# zigduino-v6c-test.net
KiCad netlist of a schematic drawn in EAGLE
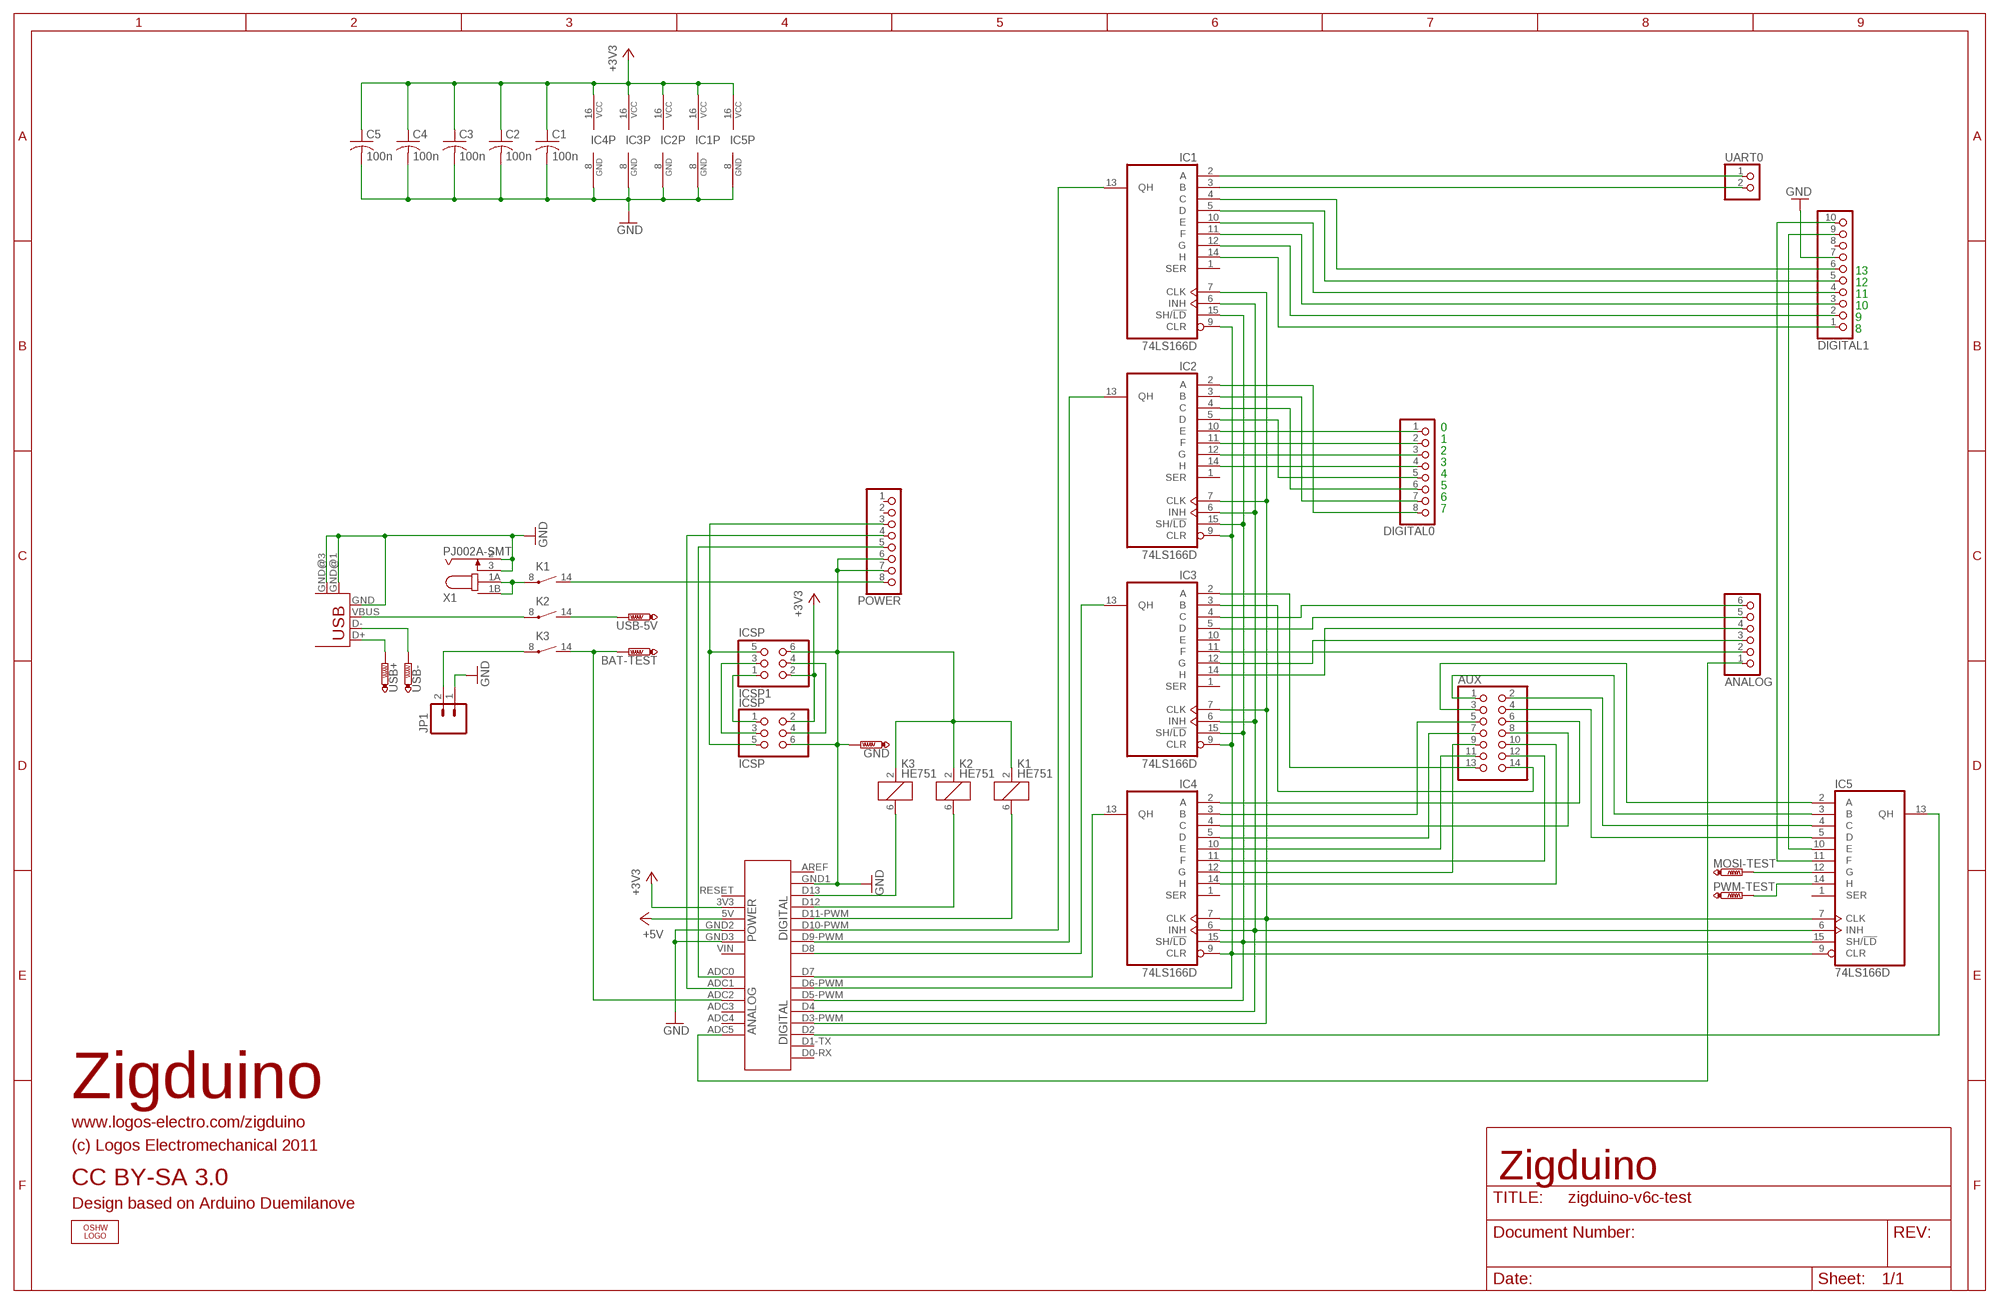
[diagram p0: schematic, sheet 1]

(export (version "E")
  (design (tool "Eeschema 10.0.6"))
  (components
    (comp (ref "ANALOG")
      (value "PINHD-1X6")
      (footprint "eagle-import:1X06")
      (fields (field (name "PARTNO") "19742"))
      (libsource (lib "eagle-import") (part "PINHD-1X6"))
    )
    (comp (ref "AUX")
      (value "PINHD-2X7_2.00")
      (footprint "eagle-import:2X07M")
      (fields (field (name "PARTNO") "00217"))
      (libsource (lib "eagle-import") (part "PINHD-2X7_2.00"))
    )
    (comp (ref "BAT-TEST")
      (value "PTR1PAD1-13")
      (footprint "eagle-import:P1-13")
      (fields (field (name "PARTNO") "TP13"))
      (libsource (lib "eagle-import") (part "PTR1PAD1-13"))
    )
    (comp (ref "C1")
      (value "100n")
      (footprint "eagle-import:C0603")
      (libsource (lib "eagle-import") (part "C-USC0603"))
    )
    (comp (ref "C2")
      (value "100n")
      (footprint "eagle-import:C0603")
      (libsource (lib "eagle-import") (part "C-USC0603"))
    )
    (comp (ref "C3")
      (value "100n")
      (footprint "eagle-import:C0603")
      (libsource (lib "eagle-import") (part "C-USC0603"))
    )
    (comp (ref "C4")
      (value "100n")
      (footprint "eagle-import:C0603")
      (libsource (lib "eagle-import") (part "C-USC0603"))
    )
    (comp (ref "C5")
      (value "100n")
      (footprint "eagle-import:C0603")
      (libsource (lib "eagle-import") (part "C-USC0603"))
    )
    (comp (ref "DIGITAL0")
      (value "PINHD-1X8")
      (footprint "eagle-import:1X08")
      (fields (field (name "PARTNO") "19743"))
      (libsource (lib "eagle-import") (part "PINHD-1X8"))
    )
    (comp (ref "DIGITAL1")
      (value "PINHD-1X10")
      (footprint "eagle-import:1X10")
      (fields (field (name "PARTNO") "20083"))
      (libsource (lib "eagle-import") (part "PINHD-1X10"))
    )
    (comp (ref "GND")
      (value "PTR1PAD1-13")
      (footprint "eagle-import:P1-13")
      (fields (field (name "PARTNO") "TP13"))
      (libsource (lib "eagle-import") (part "PTR1PAD1-13"))
    )
    (comp (ref "IC1")
      (value "74LS166D")
      (footprint "eagle-import:SO16")
      (libsource (lib "eagle-import") (part "74166DLS"))
    )
    (comp (ref "IC2")
      (value "74LS166D")
      (footprint "eagle-import:SO16")
      (libsource (lib "eagle-import") (part "74166DLS"))
    )
    (comp (ref "IC3")
      (value "74LS166D")
      (footprint "eagle-import:SO16")
      (libsource (lib "eagle-import") (part "74166DLS"))
    )
    (comp (ref "IC4")
      (value "74LS166D")
      (footprint "eagle-import:SO16")
      (libsource (lib "eagle-import") (part "74166DLS"))
    )
    (comp (ref "IC5")
      (value "74LS166D")
      (footprint "eagle-import:SO16")
      (libsource (lib "eagle-import") (part "74166DLS"))
    )
    (comp (ref "ICSP")
      (value "ICSP")
      (footprint "eagle-import:2X03")
      (fields (field (name "PARTNO") "961206-6404-AR"))
      (libsource (lib "eagle-import") (part "PINHD-2X3"))
    )
    (comp (ref "ICSP1")
      (value "ICSP")
      (footprint "eagle-import:2X03")
      (fields (field (name "PARTNO") "961206-6404-AR"))
      (libsource (lib "eagle-import") (part "PINHD-2X3"))
    )
    (comp (ref "JP1")
      (value "M02-JST-2MM-SMT")
      (footprint "eagle-import:S2B-PH")
      (libsource (lib "eagle-import") (part "M02-JST-2MM-SMT"))
    )
    (comp (ref "K1")
      (value "HE751")
      (footprint "eagle-import:HE751")
      (libsource (lib "eagle-import") (part "HE751"))
    )
    (comp (ref "K2")
      (value "HE751")
      (footprint "eagle-import:HE751")
      (libsource (lib "eagle-import") (part "HE751"))
    )
    (comp (ref "K3")
      (value "HE751")
      (footprint "eagle-import:HE751")
      (libsource (lib "eagle-import") (part "HE751"))
    )
    (comp (ref "LOGO1")
      (value "OSHW_LOGO_FILLX0200-NT")
      (footprint "eagle-import:OSHW_FILLX200_NOTEXT")
      (libsource (lib "eagle-import") (part "OSHW_LOGO_FILLX0200-NT"))
    )
    (comp (ref "MOSI-TEST")
      (value "PTR1PAD1-13")
      (footprint "eagle-import:P1-13")
      (fields (field (name "PARTNO") "TP13"))
      (libsource (lib "eagle-import") (part "PTR1PAD1-13"))
    )
    (comp (ref "POWER")
      (value "PINHD-1X8")
      (footprint "eagle-import:1X08")
      (fields (field (name "PARTNO") "19743"))
      (libsource (lib "eagle-import") (part "PINHD-1X8"))
    )
    (comp (ref "PWM-TEST")
      (value "PTR1PAD1-13")
      (footprint "eagle-import:P1-13")
      (fields (field (name "PARTNO") "TP13"))
      (libsource (lib "eagle-import") (part "PTR1PAD1-13"))
    )
    (comp (ref "SHIELD1")
      (value "2009")
      (footprint "eagle-import:2009")
      (libsource (lib "eagle-import") (part "2009"))
    )
    (comp (ref "UART0")
      (value "PINHD-1X2")
      (footprint "eagle-import:1X02")
      (fields (field (name "PARTNO") "00522"))
      (libsource (lib "eagle-import") (part "PINHD-1X2"))
    )
    (comp (ref "USB+")
      (value "PTR1PAD1-13")
      (footprint "eagle-import:P1-13")
      (fields (field (name "PARTNO") "TP13"))
      (libsource (lib "eagle-import") (part "PTR1PAD1-13"))
    )
    (comp (ref "USB-")
      (value "PTR1PAD1-13")
      (footprint "eagle-import:P1-13")
      (fields (field (name "PARTNO") "TP13"))
      (libsource (lib "eagle-import") (part "PTR1PAD1-13"))
    )
    (comp (ref "USB-5V")
      (value "PTR1PAD1-13")
      (footprint "eagle-import:P1-13")
      (fields (field (name "PARTNO") "TP13"))
      (libsource (lib "eagle-import") (part "PTR1PAD1-13"))
    )
    (comp (ref "USB1")
      (value "USB-MB-S")
      (footprint "eagle-import:USB-MB-S")
      (libsource (lib "eagle-import") (part "USB-MB-S"))
    )
    (comp (ref "X1")
      (value "PJ002A-SMT")
      (footprint "eagle-import:PJ002A-SMT")
      (libsource (lib "eagle-import") (part "PJ002A-SMT"))
    )
  )
  (nets
    (net (code "1") (name "+3V3") (class "Default")
      (node (ref "C1") (pin "1") (pinfunction "1_1") (pintype "passive"))
      (node (ref "C2") (pin "1") (pinfunction "1_1") (pintype "passive"))
      (node (ref "C3") (pin "1") (pinfunction "1_1") (pintype "passive"))
      (node (ref "C4") (pin "1") (pinfunction "1_1") (pintype "passive"))
      (node (ref "C5") (pin "1") (pinfunction "1_1") (pintype "passive"))
      (node (ref "IC1") (pin "16") (pinfunction "VCC_16") (pintype "power_in"))
      (node (ref "IC2") (pin "16") (pinfunction "VCC_16") (pintype "power_in"))
      (node (ref "IC3") (pin "16") (pinfunction "VCC_16") (pintype "power_in"))
      (node (ref "IC4") (pin "16") (pinfunction "VCC_16") (pintype "power_in"))
      (node (ref "IC5") (pin "16") (pinfunction "VCC_16") (pintype "power_in"))
      (node (ref "ICSP") (pin "2") (pinfunction "2_2") (pintype "passive"))
      (node (ref "ICSP1") (pin "2") (pinfunction "2_2") (pintype "passive"))
      (node (ref "SHIELD1") (pin "3V3") (pinfunction "3V3_3V3") (pintype "bidirectional"))
    )
    (net (code "2") (name "+5V") (class "Default")
      (node (ref "SHIELD1") (pin "5V") (pinfunction "5V_5V") (pintype "bidirectional"))
    )
    (net (code "3") (name "GND") (class "Default")
      (node (ref "C1") (pin "2") (pinfunction "2_2") (pintype "passive"))
      (node (ref "C2") (pin "2") (pinfunction "2_2") (pintype "passive"))
      (node (ref "C3") (pin "2") (pinfunction "2_2") (pintype "passive"))
      (node (ref "C4") (pin "2") (pinfunction "2_2") (pintype "passive"))
      (node (ref "C5") (pin "2") (pinfunction "2_2") (pintype "passive"))
      (node (ref "DIGITAL1") (pin "7") (pinfunction "7_7") (pintype "passive"))
      (node (ref "GND") (pin "TP") (pinfunction "TP_TP") (pintype "input"))
      (node (ref "IC1") (pin "8") (pinfunction "GND_8") (pintype "power_in"))
      (node (ref "IC2") (pin "8") (pinfunction "GND_8") (pintype "power_in"))
      (node (ref "IC3") (pin "8") (pinfunction "GND_8") (pintype "power_in"))
      (node (ref "IC4") (pin "8") (pinfunction "GND_8") (pintype "power_in"))
      (node (ref "IC5") (pin "8") (pinfunction "GND_8") (pintype "power_in"))
      (node (ref "ICSP") (pin "6") (pinfunction "6_6") (pintype "passive"))
      (node (ref "ICSP1") (pin "6") (pinfunction "6_6") (pintype "passive"))
      (node (ref "JP1") (pin "1") (pinfunction "1_1") (pintype "passive"))
      (node (ref "K1") (pin "2") (pinfunction "1_2") (pintype "passive"))
      (node (ref "K2") (pin "2") (pinfunction "1_2") (pintype "passive"))
      (node (ref "K3") (pin "2") (pinfunction "1_2") (pintype "passive"))
      (node (ref "POWER") (pin "6") (pinfunction "6_6") (pintype "passive"))
      (node (ref "POWER") (pin "7") (pinfunction "7_7") (pintype "passive"))
      (node (ref "SHIELD1") (pin "GND1") (pinfunction "GND1_GND1") (pintype "bidirectional"))
      (node (ref "SHIELD1") (pin "GND2") (pinfunction "GND2_GND2") (pintype "bidirectional"))
      (node (ref "SHIELD1") (pin "GND3") (pinfunction "GND3_GND3") (pintype "bidirectional"))
      (node (ref "USB1") (pin "GND") (pinfunction "GND_GND") (pintype "bidirectional"))
      (node (ref "USB1") (pin "GND@1") (pinfunction "GND_GND@1") (pintype "bidirectional"))
      (node (ref "USB1") (pin "GND@3") (pinfunction "GND_GND@3") (pintype "bidirectional"))
      (node (ref "X1") (pin "2") (pinfunction "2_2") (pintype "passive"))
      (node (ref "X1") (pin "3") (pinfunction "3_3") (pintype "passive"))
    )
    (net (code "4") (name "Net-(ANALOG-Pad1)") (class "Default")
      (node (ref "ANALOG") (pin "1") (pinfunction "1_1") (pintype "passive"))
      (node (ref "SHIELD1") (pin "ADC5") (pinfunction "ADC5_ADC5") (pintype "bidirectional"))
    )
    (net (code "5") (name "Net-(IC1A-A)") (class "Default")
      (node (ref "IC1") (pin "2") (pinfunction "A_2") (pintype "input"))
      (node (ref "UART0") (pin "1") (pinfunction "1_1") (pintype "passive"))
    )
    (net (code "6") (name "Net-(IC1A-B)") (class "Default")
      (node (ref "IC1") (pin "3") (pinfunction "B_3") (pintype "input"))
      (node (ref "UART0") (pin "2") (pinfunction "2_2") (pintype "passive"))
    )
    (net (code "7") (name "Net-(IC1A-C)") (class "Default")
      (node (ref "DIGITAL1") (pin "6") (pinfunction "6_6") (pintype "passive"))
      (node (ref "IC1") (pin "4") (pinfunction "C_4") (pintype "input"))
    )
    (net (code "8") (name "Net-(IC1A-CLK)") (class "Default")
      (node (ref "IC1") (pin "7") (pinfunction "CLK_7") (pintype "input"))
      (node (ref "IC2") (pin "7") (pinfunction "CLK_7") (pintype "input"))
      (node (ref "IC3") (pin "7") (pinfunction "CLK_7") (pintype "input"))
      (node (ref "IC4") (pin "7") (pinfunction "CLK_7") (pintype "input"))
      (node (ref "IC5") (pin "7") (pinfunction "CLK_7") (pintype "input"))
      (node (ref "SHIELD1") (pin "D3-PWM") (pinfunction "D3_D3-PWM") (pintype "bidirectional"))
    )
    (net (code "9") (name "Net-(IC1A-CLR)") (class "Default")
      (node (ref "IC1") (pin "9") (pinfunction "CLR_9") (pintype "input"))
      (node (ref "IC2") (pin "9") (pinfunction "CLR_9") (pintype "input"))
      (node (ref "IC3") (pin "9") (pinfunction "CLR_9") (pintype "input"))
      (node (ref "IC4") (pin "9") (pinfunction "CLR_9") (pintype "input"))
      (node (ref "IC5") (pin "9") (pinfunction "CLR_9") (pintype "input"))
      (node (ref "SHIELD1") (pin "D6-PWM") (pinfunction "D6_D6-PWM") (pintype "bidirectional"))
    )
    (net (code "10") (name "Net-(IC1A-D)") (class "Default")
      (node (ref "DIGITAL1") (pin "5") (pinfunction "5_5") (pintype "passive"))
      (node (ref "IC1") (pin "5") (pinfunction "D_5") (pintype "input"))
    )
    (net (code "11") (name "Net-(IC1A-E)") (class "Default")
      (node (ref "DIGITAL1") (pin "4") (pinfunction "4_4") (pintype "passive"))
      (node (ref "IC1") (pin "10") (pinfunction "E_10") (pintype "input"))
    )
    (net (code "12") (name "Net-(IC1A-F)") (class "Default")
      (node (ref "DIGITAL1") (pin "3") (pinfunction "3_3") (pintype "passive"))
      (node (ref "IC1") (pin "11") (pinfunction "F_11") (pintype "input"))
    )
    (net (code "13") (name "Net-(IC1A-G)") (class "Default")
      (node (ref "DIGITAL1") (pin "2") (pinfunction "2_2") (pintype "passive"))
      (node (ref "IC1") (pin "12") (pinfunction "G_12") (pintype "input"))
    )
    (net (code "14") (name "Net-(IC1A-H)") (class "Default")
      (node (ref "DIGITAL1") (pin "1") (pinfunction "1_1") (pintype "passive"))
      (node (ref "IC1") (pin "14") (pinfunction "H_14") (pintype "input"))
    )
    (net (code "15") (name "Net-(IC1A-INH)") (class "Default")
      (node (ref "IC1") (pin "6") (pinfunction "INH_6") (pintype "input"))
      (node (ref "IC2") (pin "6") (pinfunction "INH_6") (pintype "input"))
      (node (ref "IC3") (pin "6") (pinfunction "INH_6") (pintype "input"))
      (node (ref "IC4") (pin "6") (pinfunction "INH_6") (pintype "input"))
      (node (ref "IC5") (pin "6") (pinfunction "INH_6") (pintype "input"))
      (node (ref "SHIELD1") (pin "D4") (pinfunction "D4_D4") (pintype "bidirectional"))
    )
    (net (code "16") (name "Net-(IC1A-QH)") (class "Default")
      (node (ref "IC1") (pin "13") (pinfunction "QH_13") (pintype "output"))
      (node (ref "SHIELD1") (pin "D10-PWM") (pinfunction "D10_D10-PWM") (pintype "bidirectional"))
    )
    (net (code "17") (name "Net-(IC1A-SH{slash}~{LD})") (class "Default")
      (node (ref "IC1") (pin "15") (pinfunction "SH/~{LD}_15") (pintype "input"))
      (node (ref "IC2") (pin "15") (pinfunction "SH/~{LD}_15") (pintype "input"))
      (node (ref "IC3") (pin "15") (pinfunction "SH/~{LD}_15") (pintype "input"))
      (node (ref "IC4") (pin "15") (pinfunction "SH/~{LD}_15") (pintype "input"))
      (node (ref "IC5") (pin "15") (pinfunction "SH/~{LD}_15") (pintype "input"))
      (node (ref "SHIELD1") (pin "D5-PWM") (pinfunction "D5_D5-PWM") (pintype "bidirectional"))
    )
    (net (code "18") (name "Net-(IC2A-A)") (class "Default")
      (node (ref "DIGITAL0") (pin "8") (pinfunction "8_8") (pintype "passive"))
      (node (ref "IC2") (pin "2") (pinfunction "A_2") (pintype "input"))
    )
    (net (code "19") (name "Net-(IC2A-B)") (class "Default")
      (node (ref "DIGITAL0") (pin "7") (pinfunction "7_7") (pintype "passive"))
      (node (ref "IC2") (pin "3") (pinfunction "B_3") (pintype "input"))
    )
    (net (code "20") (name "Net-(IC2A-C)") (class "Default")
      (node (ref "DIGITAL0") (pin "6") (pinfunction "6_6") (pintype "passive"))
      (node (ref "IC2") (pin "4") (pinfunction "C_4") (pintype "input"))
    )
    (net (code "21") (name "Net-(IC2A-D)") (class "Default")
      (node (ref "DIGITAL0") (pin "5") (pinfunction "5_5") (pintype "passive"))
      (node (ref "IC2") (pin "5") (pinfunction "D_5") (pintype "input"))
    )
    (net (code "22") (name "Net-(IC2A-E)") (class "Default")
      (node (ref "DIGITAL0") (pin "1") (pinfunction "1_1") (pintype "passive"))
      (node (ref "IC2") (pin "10") (pinfunction "E_10") (pintype "input"))
    )
    (net (code "23") (name "Net-(IC2A-F)") (class "Default")
      (node (ref "DIGITAL0") (pin "2") (pinfunction "2_2") (pintype "passive"))
      (node (ref "IC2") (pin "11") (pinfunction "F_11") (pintype "input"))
    )
    (net (code "24") (name "Net-(IC2A-G)") (class "Default")
      (node (ref "DIGITAL0") (pin "3") (pinfunction "3_3") (pintype "passive"))
      (node (ref "IC2") (pin "12") (pinfunction "G_12") (pintype "input"))
    )
    (net (code "25") (name "Net-(IC2A-H)") (class "Default")
      (node (ref "DIGITAL0") (pin "4") (pinfunction "4_4") (pintype "passive"))
      (node (ref "IC2") (pin "14") (pinfunction "H_14") (pintype "input"))
    )
    (net (code "26") (name "Net-(IC2A-QH)") (class "Default")
      (node (ref "IC2") (pin "13") (pinfunction "QH_13") (pintype "output"))
      (node (ref "SHIELD1") (pin "D9-PWM") (pinfunction "D9_D9-PWM") (pintype "bidirectional"))
    )
    (net (code "27") (name "Net-(IC3A-A)") (class "Default")
      (node (ref "AUX") (pin "13") (pinfunction "13_13") (pintype "passive"))
      (node (ref "IC3") (pin "2") (pinfunction "A_2") (pintype "input"))
    )
    (net (code "28") (name "Net-(IC3A-B)") (class "Default")
      (node (ref "AUX") (pin "14") (pinfunction "14_14") (pintype "passive"))
      (node (ref "IC3") (pin "3") (pinfunction "B_3") (pintype "input"))
    )
    (net (code "29") (name "Net-(IC3A-C)") (class "Default")
      (node (ref "ANALOG") (pin "6") (pinfunction "6_6") (pintype "passive"))
      (node (ref "IC3") (pin "4") (pinfunction "C_4") (pintype "input"))
    )
    (net (code "30") (name "Net-(IC3A-D)") (class "Default")
      (node (ref "ANALOG") (pin "5") (pinfunction "5_5") (pintype "passive"))
      (node (ref "IC3") (pin "5") (pinfunction "D_5") (pintype "input"))
    )
    (net (code "31") (name "Net-(IC3A-F)") (class "Default")
      (node (ref "ANALOG") (pin "2") (pinfunction "2_2") (pintype "passive"))
      (node (ref "IC3") (pin "11") (pinfunction "F_11") (pintype "input"))
    )
    (net (code "32") (name "Net-(IC3A-G)") (class "Default")
      (node (ref "ANALOG") (pin "3") (pinfunction "3_3") (pintype "passive"))
      (node (ref "IC3") (pin "12") (pinfunction "G_12") (pintype "input"))
    )
    (net (code "33") (name "Net-(IC3A-H)") (class "Default")
      (node (ref "ANALOG") (pin "4") (pinfunction "4_4") (pintype "passive"))
      (node (ref "IC3") (pin "14") (pinfunction "H_14") (pintype "input"))
    )
    (net (code "34") (name "Net-(IC3A-QH)") (class "Default")
      (node (ref "IC3") (pin "13") (pinfunction "QH_13") (pintype "output"))
      (node (ref "SHIELD1") (pin "D8") (pinfunction "D8_D8") (pintype "bidirectional"))
    )
    (net (code "35") (name "Net-(IC4A-A)") (class "Default")
      (node (ref "AUX") (pin "6") (pinfunction "6_6") (pintype "passive"))
      (node (ref "IC4") (pin "2") (pinfunction "A_2") (pintype "input"))
    )
    (net (code "36") (name "Net-(IC4A-B)") (class "Default")
      (node (ref "AUX") (pin "5") (pinfunction "5_5") (pintype "passive"))
      (node (ref "IC4") (pin "3") (pinfunction "B_3") (pintype "input"))
    )
    (net (code "37") (name "Net-(IC4A-C)") (class "Default")
      (node (ref "AUX") (pin "8") (pinfunction "8_8") (pintype "passive"))
      (node (ref "IC4") (pin "4") (pinfunction "C_4") (pintype "input"))
    )
    (net (code "38") (name "Net-(IC4A-D)") (class "Default")
      (node (ref "AUX") (pin "7") (pinfunction "7_7") (pintype "passive"))
      (node (ref "IC4") (pin "5") (pinfunction "D_5") (pintype "input"))
    )
    (net (code "39") (name "Net-(IC4A-E)") (class "Default")
      (node (ref "AUX") (pin "11") (pinfunction "11_11") (pintype "passive"))
      (node (ref "IC4") (pin "10") (pinfunction "E_10") (pintype "input"))
    )
    (net (code "40") (name "Net-(IC4A-F)") (class "Default")
      (node (ref "AUX") (pin "12") (pinfunction "12_12") (pintype "passive"))
      (node (ref "IC4") (pin "11") (pinfunction "F_11") (pintype "input"))
    )
    (net (code "41") (name "Net-(IC4A-G)") (class "Default")
      (node (ref "AUX") (pin "9") (pinfunction "9_9") (pintype "passive"))
      (node (ref "IC4") (pin "12") (pinfunction "G_12") (pintype "input"))
    )
    (net (code "42") (name "Net-(IC4A-H)") (class "Default")
      (node (ref "AUX") (pin "10") (pinfunction "10_10") (pintype "passive"))
      (node (ref "IC4") (pin "14") (pinfunction "H_14") (pintype "input"))
    )
    (net (code "43") (name "Net-(IC4A-QH)") (class "Default")
      (node (ref "IC4") (pin "13") (pinfunction "QH_13") (pintype "output"))
      (node (ref "SHIELD1") (pin "D7") (pinfunction "D7_D7") (pintype "bidirectional"))
    )
    (net (code "44") (name "Net-(IC5A-A)") (class "Default")
      (node (ref "AUX") (pin "3") (pinfunction "3_3") (pintype "passive"))
      (node (ref "IC5") (pin "2") (pinfunction "A_2") (pintype "input"))
    )
    (net (code "45") (name "Net-(IC5A-B)") (class "Default")
      (node (ref "AUX") (pin "1") (pinfunction "1_1") (pintype "passive"))
      (node (ref "IC5") (pin "3") (pinfunction "B_3") (pintype "input"))
    )
    (net (code "46") (name "Net-(IC5A-C)") (class "Default")
      (node (ref "AUX") (pin "2") (pinfunction "2_2") (pintype "passive"))
      (node (ref "IC5") (pin "4") (pinfunction "C_4") (pintype "input"))
    )
    (net (code "47") (name "Net-(IC5A-D)") (class "Default")
      (node (ref "AUX") (pin "4") (pinfunction "4_4") (pintype "passive"))
      (node (ref "IC5") (pin "5") (pinfunction "D_5") (pintype "input"))
    )
    (net (code "48") (name "Net-(IC5A-E)") (class "Default")
      (node (ref "DIGITAL1") (pin "9") (pinfunction "9_9") (pintype "passive"))
      (node (ref "IC5") (pin "10") (pinfunction "E_10") (pintype "input"))
    )
    (net (code "49") (name "Net-(IC5A-F)") (class "Default")
      (node (ref "DIGITAL1") (pin "10") (pinfunction "10_10") (pintype "passive"))
      (node (ref "IC5") (pin "11") (pinfunction "F_11") (pintype "input"))
    )
    (net (code "50") (name "Net-(IC5A-G)") (class "Default")
      (node (ref "IC5") (pin "12") (pinfunction "G_12") (pintype "input"))
      (node (ref "MOSI-TEST") (pin "TP") (pinfunction "TP_TP") (pintype "input"))
    )
    (net (code "51") (name "Net-(IC5A-H)") (class "Default")
      (node (ref "IC5") (pin "14") (pinfunction "H_14") (pintype "input"))
      (node (ref "PWM-TEST") (pin "TP") (pinfunction "TP_TP") (pintype "input"))
    )
    (net (code "52") (name "Net-(IC5A-QH)") (class "Default")
      (node (ref "IC5") (pin "13") (pinfunction "QH_13") (pintype "output"))
      (node (ref "SHIELD1") (pin "D2") (pinfunction "D2_D2") (pintype "bidirectional"))
    )
    (net (code "53") (name "Net-(ICSP-Pad1)") (class "Default")
      (node (ref "ICSP") (pin "1") (pinfunction "1_1") (pintype "passive"))
      (node (ref "ICSP1") (pin "1") (pinfunction "1_1") (pintype "passive"))
    )
    (net (code "54") (name "Net-(ICSP-Pad3)") (class "Default")
      (node (ref "ICSP") (pin "3") (pinfunction "3_3") (pintype "passive"))
      (node (ref "ICSP1") (pin "3") (pinfunction "3_3") (pintype "passive"))
    )
    (net (code "55") (name "Net-(ICSP-Pad4)") (class "Default")
      (node (ref "ICSP") (pin "4") (pinfunction "4_4") (pintype "passive"))
      (node (ref "ICSP1") (pin "4") (pinfunction "4_4") (pintype "passive"))
    )
    (net (code "56") (name "Net-(ICSP-Pad5)") (class "Default")
      (node (ref "ICSP") (pin "5") (pinfunction "5_5") (pintype "passive"))
      (node (ref "ICSP1") (pin "5") (pinfunction "5_5") (pintype "passive"))
      (node (ref "POWER") (pin "3") (pinfunction "3_3") (pintype "passive"))
    )
    (net (code "57") (name "Net-(K1A-2)") (class "Default")
      (node (ref "K1") (pin "6") (pinfunction "2_6") (pintype "passive"))
      (node (ref "SHIELD1") (pin "D11-PWM") (pinfunction "D11_D11-PWM") (pintype "bidirectional"))
    )
    (net (code "58") (name "Net-(K1B-P)") (class "Default")
      (node (ref "K1") (pin "8") (pinfunction "P_8") (pintype "passive"))
      (node (ref "X1") (pin "1A") (pinfunction "1A_1A") (pintype "passive"))
      (node (ref "X1") (pin "1B") (pinfunction "1B_1B") (pintype "passive"))
    )
    (net (code "59") (name "Net-(K1B-S)") (class "Default")
      (node (ref "K1") (pin "14") (pinfunction "S_14") (pintype "passive"))
      (node (ref "POWER") (pin "8") (pinfunction "8_8") (pintype "passive"))
    )
    (net (code "60") (name "Net-(K2A-2)") (class "Default")
      (node (ref "K2") (pin "6") (pinfunction "2_6") (pintype "passive"))
      (node (ref "SHIELD1") (pin "D12") (pinfunction "D12_D12") (pintype "bidirectional"))
    )
    (net (code "61") (name "Net-(K2B-P)") (class "Default")
      (node (ref "K2") (pin "8") (pinfunction "P_8") (pintype "passive"))
      (node (ref "USB1") (pin "VBUS") (pinfunction "VBUS_VBUS") (pintype "bidirectional"))
    )
    (net (code "62") (name "Net-(K2B-S)") (class "Default")
      (node (ref "K2") (pin "14") (pinfunction "S_14") (pintype "passive"))
      (node (ref "USB-5V") (pin "TP") (pinfunction "TP_TP") (pintype "input"))
    )
    (net (code "63") (name "Net-(K3A-2)") (class "Default")
      (node (ref "K3") (pin "6") (pinfunction "2_6") (pintype "passive"))
      (node (ref "SHIELD1") (pin "D13") (pinfunction "D13_D13") (pintype "bidirectional"))
    )
    (net (code "64") (name "Net-(K3B-P)") (class "Default")
      (node (ref "JP1") (pin "2") (pinfunction "2_2") (pintype "passive"))
      (node (ref "K3") (pin "8") (pinfunction "P_8") (pintype "passive"))
    )
    (net (code "65") (name "Net-(K3B-S)") (class "Default")
      (node (ref "BAT-TEST") (pin "TP") (pinfunction "TP_TP") (pintype "input"))
      (node (ref "K3") (pin "14") (pinfunction "S_14") (pintype "passive"))
      (node (ref "SHIELD1") (pin "ADC2") (pinfunction "ADC2_ADC2") (pintype "bidirectional"))
    )
    (net (code "66") (name "Net-(POWER-Pad4)") (class "Default")
      (node (ref "POWER") (pin "4") (pinfunction "4_4") (pintype "passive"))
      (node (ref "SHIELD1") (pin "ADC1") (pinfunction "ADC1_ADC1") (pintype "bidirectional"))
    )
    (net (code "67") (name "Net-(POWER-Pad5)") (class "Default")
      (node (ref "POWER") (pin "5") (pinfunction "5_5") (pintype "passive"))
      (node (ref "SHIELD1") (pin "ADC0") (pinfunction "ADC0_ADC0") (pintype "bidirectional"))
    )
    (net (code "68") (name "Net-(USB+-PadTP)") (class "Default")
      (node (ref "USB+") (pin "TP") (pinfunction "TP_TP") (pintype "input"))
      (node (ref "USB1") (pin "D+") (pinfunction "D+_D+") (pintype "bidirectional"))
    )
    (net (code "69") (name "Net-(USB--PadTP)") (class "Default")
      (node (ref "USB-") (pin "TP") (pinfunction "TP_TP") (pintype "input"))
      (node (ref "USB1") (pin "D-") (pinfunction "D-_D-") (pintype "bidirectional"))
    )
    (net (code "70") (name "unconnected-(DIGITAL1-Pad8)") (class "Default")
      (node (ref "DIGITAL1") (pin "8") (pinfunction "8_8") (pintype "passive"))
    )
    (net (code "71") (name "unconnected-(IC1A-SER-Pad1)") (class "Default")
      (node (ref "IC1") (pin "1") (pinfunction "SER_1") (pintype "input"))
    )
    (net (code "72") (name "unconnected-(IC2A-SER-Pad1)") (class "Default")
      (node (ref "IC2") (pin "1") (pinfunction "SER_1") (pintype "input"))
    )
    (net (code "73") (name "unconnected-(IC3A-E-Pad10)") (class "Default")
      (node (ref "IC3") (pin "10") (pinfunction "E_10") (pintype "input"))
    )
    (net (code "74") (name "unconnected-(IC3A-SER-Pad1)") (class "Default")
      (node (ref "IC3") (pin "1") (pinfunction "SER_1") (pintype "input"))
    )
    (net (code "75") (name "unconnected-(IC4A-SER-Pad1)") (class "Default")
      (node (ref "IC4") (pin "1") (pinfunction "SER_1") (pintype "input"))
    )
    (net (code "76") (name "unconnected-(IC5A-SER-Pad1)") (class "Default")
      (node (ref "IC5") (pin "1") (pinfunction "SER_1") (pintype "input"))
    )
    (net (code "77") (name "unconnected-(POWER-Pad1)") (class "Default")
      (node (ref "POWER") (pin "1") (pinfunction "1_1") (pintype "passive"))
    )
    (net (code "78") (name "unconnected-(POWER-Pad2)") (class "Default")
      (node (ref "POWER") (pin "2") (pinfunction "2_2") (pintype "passive"))
    )
    (net (code "79") (name "unconnected-(SHIELD1-D0-PadD0-RX)") (class "Default")
      (node (ref "SHIELD1") (pin "D0-RX") (pinfunction "D0_D0-RX") (pintype "bidirectional"))
    )
    (net (code "80") (name "unconnected-(SHIELD1-D1-PadD1-TX)") (class "Default")
      (node (ref "SHIELD1") (pin "D1-TX") (pinfunction "D1_D1-TX") (pintype "bidirectional"))
    )
    (net (code "81") (name "unconnected-(SHIELD1-PadADC3)") (class "Default")
      (node (ref "SHIELD1") (pin "ADC3") (pinfunction "ADC3_ADC3") (pintype "bidirectional"))
    )
    (net (code "82") (name "unconnected-(SHIELD1-PadADC4)") (class "Default")
      (node (ref "SHIELD1") (pin "ADC4") (pinfunction "ADC4_ADC4") (pintype "bidirectional"))
    )
    (net (code "83") (name "unconnected-(SHIELD1-PadAREF)") (class "Default")
      (node (ref "SHIELD1") (pin "AREF") (pinfunction "AREF_AREF") (pintype "bidirectional"))
    )
    (net (code "84") (name "unconnected-(SHIELD1-PadRESET)") (class "Default")
      (node (ref "SHIELD1") (pin "RESET") (pinfunction "RESET_RESET") (pintype "bidirectional"))
    )
    (net (code "85") (name "unconnected-(SHIELD1-PadVIN)") (class "Default")
      (node (ref "SHIELD1") (pin "VIN") (pinfunction "VIN_VIN") (pintype "bidirectional"))
    )
  )
)
